# MotorInterface.net
KiCad netlist of a schematic drawn in Altium Designer
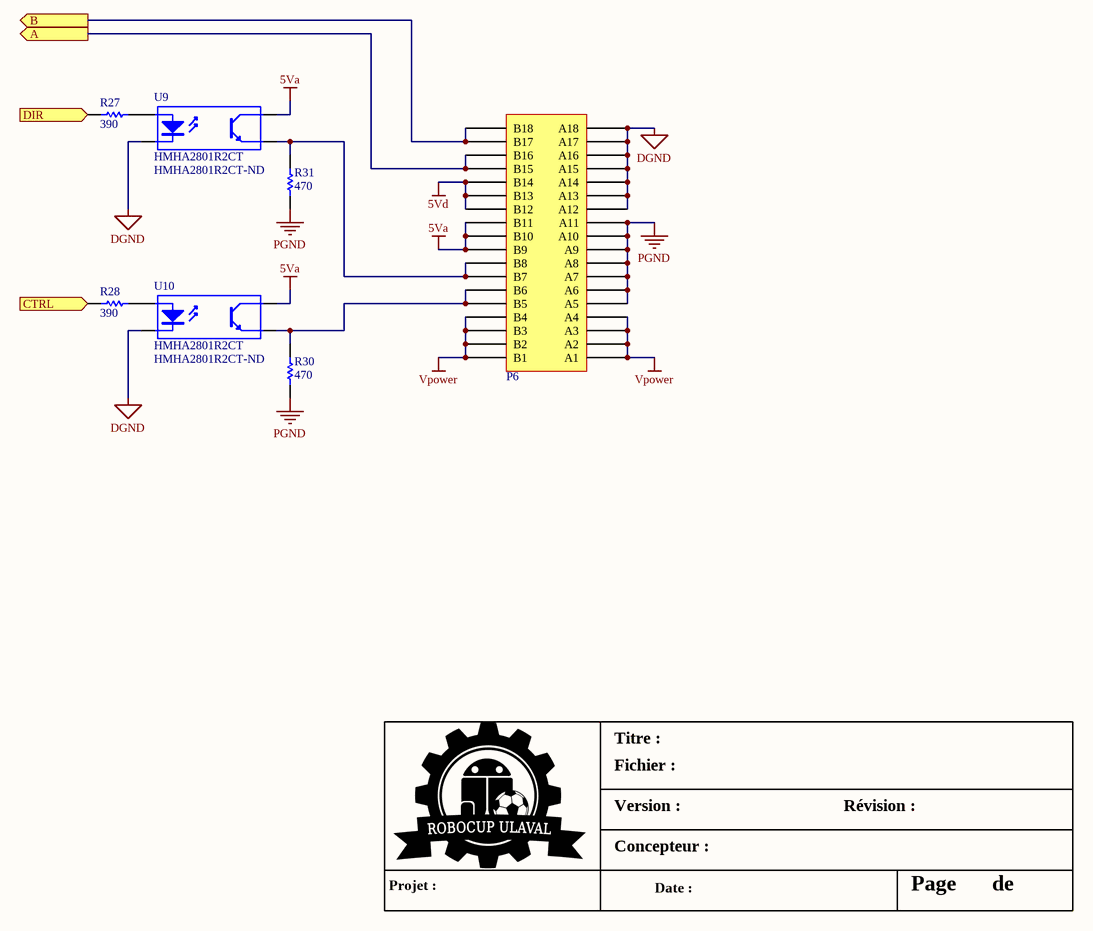
[diagram p0: MotorInterface.SchDoc]

(export (version "E")
  (design (tool "Eeschema 10.0.6"))
  (components
    (comp (ref "P6")
      (value "0877159006")
      (footprint "0877159006")
      (description "CONN PCI EXPRESS 36POS 1MM GOLD")
      (libsource (lib "MainBoard") (part "0877159006"))
    )
    (comp (ref "R27")
      (value "RC0603JR-07390RL")
      (footprint "0603")
      (description "RES SMD 390 OHM 5% 1/10W 0603")
      (fields
        (field (name "MANUFACTURER") "Yageo")
        (field (name "TOLERANCE") "±5%")
        (field (name "RESISTANCE (OHMS)") "390")
      )
      (libsource (lib "ResCap") (part "RC0603JR-07390RL"))
    )
    (comp (ref "R28")
      (value "RC0603JR-07390RL")
      (footprint "0603")
      (description "RES SMD 390 OHM 5% 1/10W 0603")
      (fields
        (field (name "MANUFACTURER") "Yageo")
        (field (name "TOLERANCE") "±5%")
        (field (name "RESISTANCE (OHMS)") "390")
      )
      (libsource (lib "ResCap") (part "RC0603JR-07390RL"))
    )
    (comp (ref "R30")
      (value "RC0603JR-07470RL")
      (footprint "0603")
      (description "RES SMD 470 OHM 5% 1/10W 0603")
      (fields
        (field (name "MANUFACTURER") "Yageo")
        (field (name "TOLERANCE") "±5%")
        (field (name "RESISTANCE (OHMS)") "470")
      )
      (libsource (lib "ResCap") (part "RC0603JR-07470RL"))
    )
    (comp (ref "R31")
      (value "RC0603JR-07470RL")
      (footprint "0603")
      (description "RES SMD 470 OHM 5% 1/10W 0603")
      (fields
        (field (name "MANUFACTURER") "Yageo")
        (field (name "TOLERANCE") "±5%")
        (field (name "RESISTANCE (OHMS)") "470")
      )
      (libsource (lib "ResCap") (part "RC0603JR-07470RL"))
    )
    (comp (ref "U9")
      (value "HMHA2801R2CT")
      (footprint "SOIC127P700X220-4N")
      (description "OPTOISOLATOR 3.75KV TRANS 4-SO")
      (fields (field (name "SUPPLIER PART NUMBER 1") "HMHA2801R2CT-ND"))
      (libsource (lib "MainBoard") (part "HMHA2801R2CT"))
    )
    (comp (ref "U10")
      (value "HMHA2801R2CT")
      (footprint "SOIC127P700X220-4N")
      (description "OPTOISOLATOR 3.75KV TRANS 4-SO")
      (fields (field (name "SUPPLIER PART NUMBER 1") "HMHA2801R2CT-ND"))
      (libsource (lib "MainBoard") (part "HMHA2801R2CT"))
    )
  )
  (nets
    (net (code "1") (name "/A") (class "Default")
      (node (ref "P6") (pin "B15") (pinfunction "B15_B15") (pintype "passive"))
      (node (ref "P6") (pin "B16") (pinfunction "B16_B16") (pintype "passive"))
    )
    (net (code "2") (name "/B") (class "Default")
      (node (ref "P6") (pin "B17") (pinfunction "B17_B17") (pintype "passive"))
      (node (ref "P6") (pin "B18") (pinfunction "B18_B18") (pintype "passive"))
    )
    (net (code "3") (name "/CTRL") (class "Default")
      (node (ref "R28") (pin "1") (pinfunction "1_1") (pintype "passive"))
    )
    (net (code "4") (name "/DIR") (class "Default")
      (node (ref "R27") (pin "1") (pinfunction "1_1") (pintype "passive"))
    )
    (net (code "5") (name "5Va") (class "Default")
      (node (ref "P6") (pin "B10") (pinfunction "B10_B10") (pintype "passive"))
      (node (ref "P6") (pin "B11") (pinfunction "B11_B11") (pintype "passive"))
      (node (ref "P6") (pin "B9") (pinfunction "B9_B9") (pintype "passive"))
      (node (ref "U10") (pin "4") (pinfunction "C_4") (pintype "passive"))
      (node (ref "U9") (pin "4") (pinfunction "C_4") (pintype "passive"))
    )
    (net (code "6") (name "5Vd") (class "Default")
      (node (ref "P6") (pin "B12") (pinfunction "B12_B12") (pintype "passive"))
      (node (ref "P6") (pin "B13") (pinfunction "B13_B13") (pintype "passive"))
      (node (ref "P6") (pin "B14") (pinfunction "B14_B14") (pintype "passive"))
    )
    (net (code "7") (name "DGND") (class "Default")
      (node (ref "P6") (pin "A12") (pinfunction "A12_A12") (pintype "passive"))
      (node (ref "P6") (pin "A13") (pinfunction "A13_A13") (pintype "passive"))
      (node (ref "P6") (pin "A14") (pinfunction "A14_A14") (pintype "passive"))
      (node (ref "P6") (pin "A15") (pinfunction "A15_A15") (pintype "passive"))
      (node (ref "P6") (pin "A16") (pinfunction "A16_A16") (pintype "passive"))
      (node (ref "P6") (pin "A17") (pinfunction "A17_A17") (pintype "passive"))
      (node (ref "P6") (pin "A18") (pinfunction "A18_A18") (pintype "passive"))
      (node (ref "U10") (pin "2") (pinfunction "K_2") (pintype "passive"))
      (node (ref "U9") (pin "2") (pinfunction "K_2") (pintype "passive"))
    )
    (net (code "8") (name "Net-(U9-A)") (class "Default")
      (node (ref "R27") (pin "2") (pinfunction "2_2") (pintype "passive"))
      (node (ref "U9") (pin "1") (pinfunction "A_1") (pintype "passive"))
    )
    (net (code "9") (name "Net-(U9-E)") (class "Default")
      (node (ref "P6") (pin "B7") (pinfunction "B7_B7") (pintype "passive"))
      (node (ref "P6") (pin "B8") (pinfunction "B8_B8") (pintype "passive"))
      (node (ref "R31") (pin "2") (pinfunction "2_2") (pintype "passive"))
      (node (ref "U9") (pin "3") (pinfunction "E_3") (pintype "passive"))
    )
    (net (code "10") (name "Net-(U10-A)") (class "Default")
      (node (ref "R28") (pin "2") (pinfunction "2_2") (pintype "passive"))
      (node (ref "U10") (pin "1") (pinfunction "A_1") (pintype "passive"))
    )
    (net (code "11") (name "Net-(U10-E)") (class "Default")
      (node (ref "P6") (pin "B5") (pinfunction "B5_B5") (pintype "passive"))
      (node (ref "P6") (pin "B6") (pinfunction "B6_B6") (pintype "passive"))
      (node (ref "R30") (pin "2") (pinfunction "2_2") (pintype "passive"))
      (node (ref "U10") (pin "3") (pinfunction "E_3") (pintype "passive"))
    )
    (net (code "12") (name "PGND") (class "Default")
      (node (ref "P6") (pin "A10") (pinfunction "A10_A10") (pintype "passive"))
      (node (ref "P6") (pin "A11") (pinfunction "A11_A11") (pintype "passive"))
      (node (ref "P6") (pin "A5") (pinfunction "A5_A5") (pintype "passive"))
      (node (ref "P6") (pin "A6") (pinfunction "A6_A6") (pintype "passive"))
      (node (ref "P6") (pin "A7") (pinfunction "A7_A7") (pintype "passive"))
      (node (ref "P6") (pin "A8") (pinfunction "A8_A8") (pintype "passive"))
      (node (ref "P6") (pin "A9") (pinfunction "A9_A9") (pintype "passive"))
      (node (ref "R30") (pin "1") (pinfunction "1_1") (pintype "passive"))
      (node (ref "R31") (pin "1") (pinfunction "1_1") (pintype "passive"))
    )
    (net (code "13") (name "Vpower") (class "Default")
      (node (ref "P6") (pin "A1") (pinfunction "A1_A1") (pintype "passive"))
      (node (ref "P6") (pin "A2") (pinfunction "A2_A2") (pintype "passive"))
      (node (ref "P6") (pin "A3") (pinfunction "A3_A3") (pintype "passive"))
      (node (ref "P6") (pin "A4") (pinfunction "A4_A4") (pintype "passive"))
      (node (ref "P6") (pin "B1") (pinfunction "B1_B1") (pintype "passive"))
      (node (ref "P6") (pin "B2") (pinfunction "B2_B2") (pintype "passive"))
      (node (ref "P6") (pin "B3") (pinfunction "B3_B3") (pintype "passive"))
      (node (ref "P6") (pin "B4") (pinfunction "B4_B4") (pintype "passive"))
    )
  )
)
